# fpc.net
KiCad netlist of a schematic drawn in EAGLE
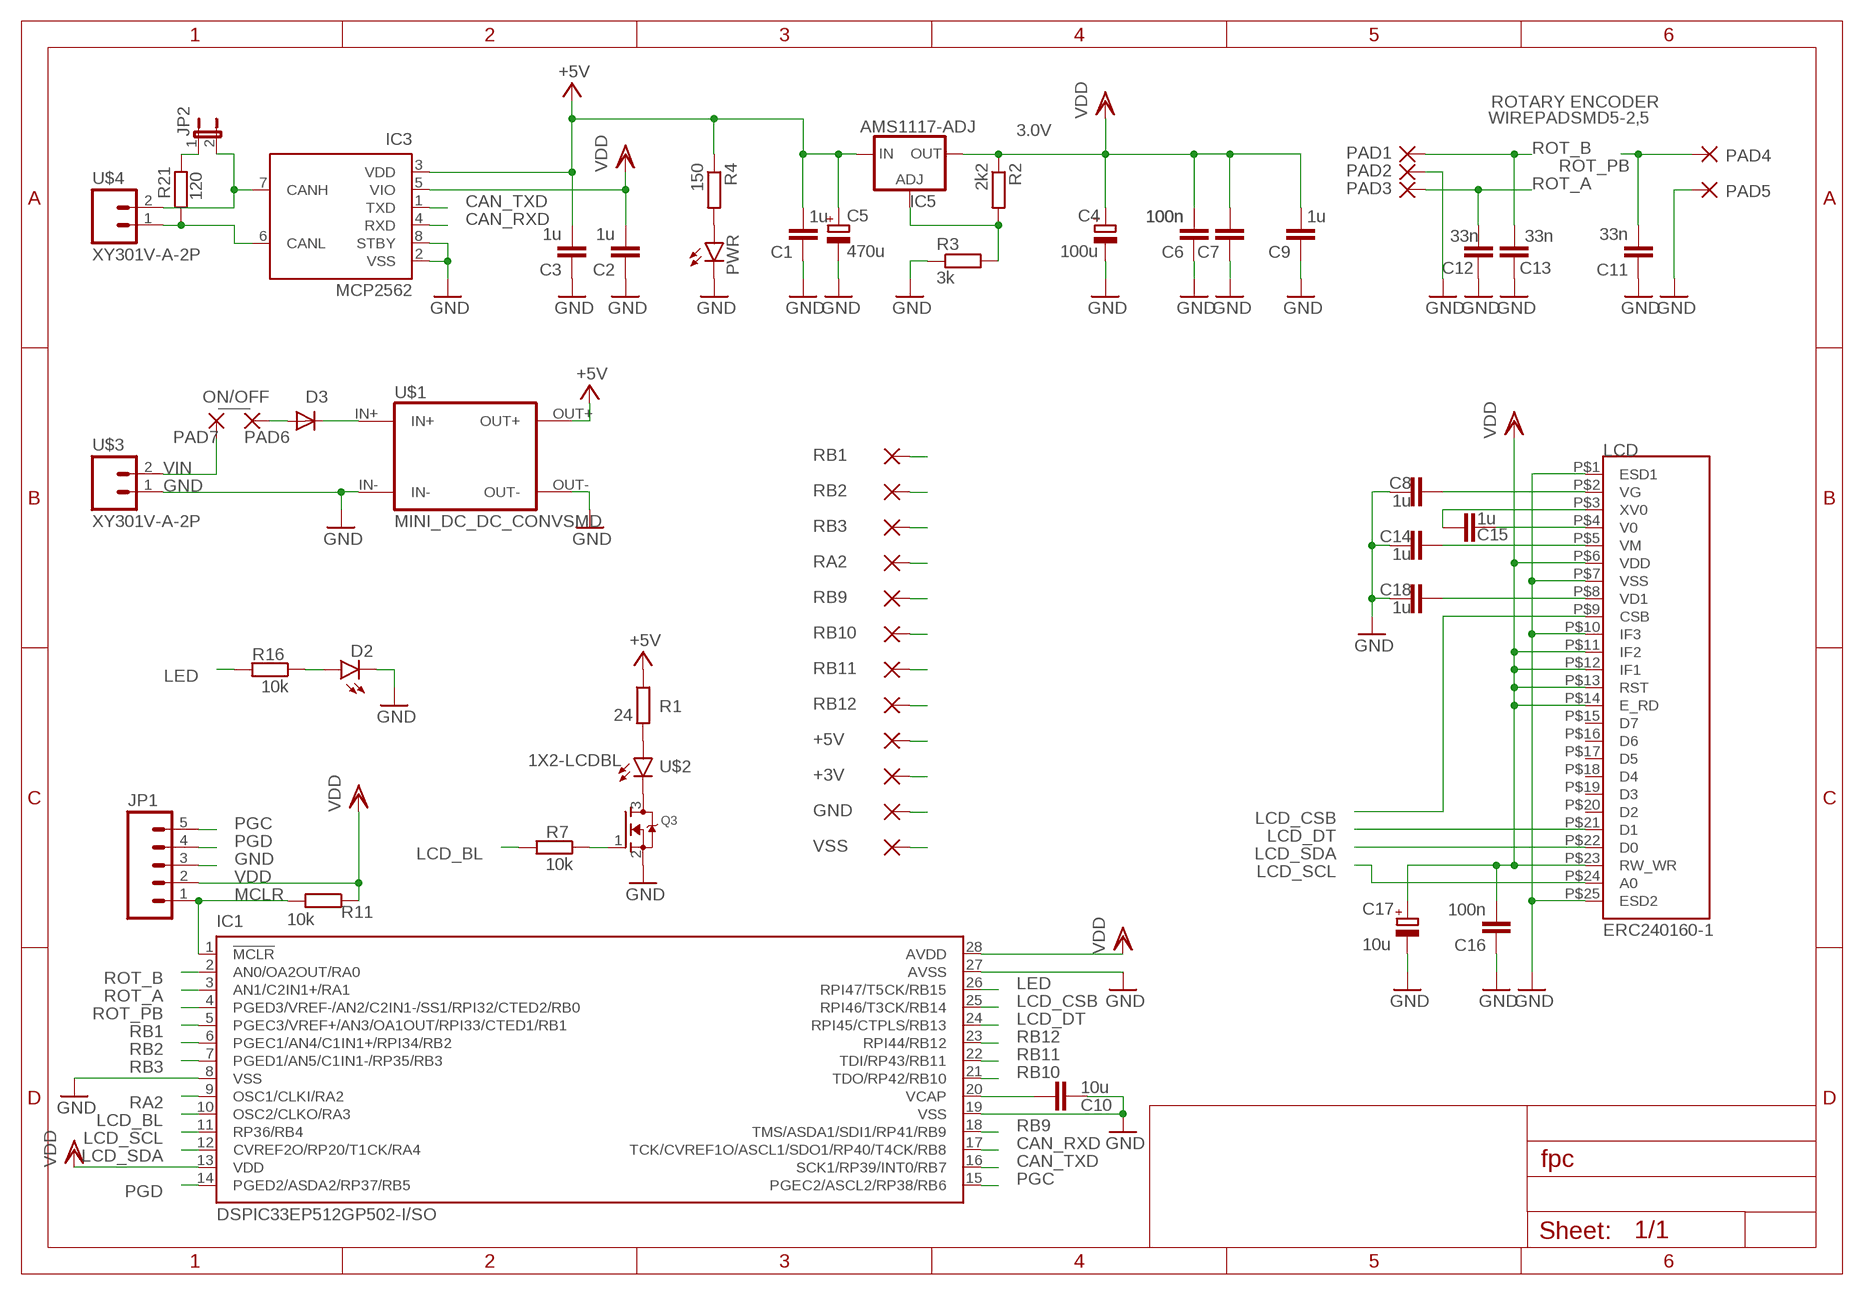
[diagram p0: schematic, sheet 1]

(export (version "E")
  (design (tool "Eeschema 10.0.6"))
  (components
    (comp (ref "+3V")
      (value "WIREPADSMD1,27-254")
      (footprint "eagle-import:SMD1,27-2,54")
      (libsource (lib "eagle-import") (part "WIREPADSMD1,27-254"))
    )
    (comp (ref "+5V")
      (value "WIREPADSMD1,27-254")
      (footprint "eagle-import:SMD1,27-2,54")
      (libsource (lib "eagle-import") (part "WIREPADSMD1,27-254"))
    )
    (comp (ref "C1")
      (value "1u")
      (footprint "eagle-import:C0603K")
      (libsource (lib "eagle-import") (part "C-EUC0603K"))
    )
    (comp (ref "C2")
      (value "1u")
      (footprint "eagle-import:C0603K")
      (libsource (lib "eagle-import") (part "C-EUC0603K"))
    )
    (comp (ref "C3")
      (value "1u")
      (footprint "eagle-import:C0603K")
      (libsource (lib "eagle-import") (part "C-EUC0603K"))
    )
    (comp (ref "C4")
      (value "100u")
      (footprint "eagle-import:SANYO-OSCON_SMD_B6")
      (libsource (lib "eagle-import") (part "CPOL-EUSANYO_SMD_B6"))
    )
    (comp (ref "C5")
      (value "470u")
      (footprint "eagle-import:SANYO-OSCON_SMD_B6")
      (libsource (lib "eagle-import") (part "CPOL-EUSANYO_SMD_B6"))
    )
    (comp (ref "C6")
      (value "100n")
      (footprint "eagle-import:C0603K")
      (libsource (lib "eagle-import") (part "C-EUC0603K"))
    )
    (comp (ref "C7")
      (value "100n")
      (footprint "eagle-import:C0603K")
      (libsource (lib "eagle-import") (part "C-EUC0603K"))
    )
    (comp (ref "C8")
      (value "1u")
      (footprint "eagle-import:C0603K")
      (libsource (lib "eagle-import") (part "C-EUC0603K"))
    )
    (comp (ref "C9")
      (value "1u")
      (footprint "eagle-import:C0603K")
      (libsource (lib "eagle-import") (part "C-EUC0603K"))
    )
    (comp (ref "C10")
      (value "10u")
      (footprint "eagle-import:C0805")
      (libsource (lib "eagle-import") (part "C-EUC0805"))
    )
    (comp (ref "C11")
      (value "33n")
      (footprint "eagle-import:C0603K")
      (libsource (lib "eagle-import") (part "C-EUC0603K"))
    )
    (comp (ref "C12")
      (value "33n")
      (footprint "eagle-import:C0603K")
      (libsource (lib "eagle-import") (part "C-EUC0603K"))
    )
    (comp (ref "C13")
      (value "33n")
      (footprint "eagle-import:C0603K")
      (libsource (lib "eagle-import") (part "C-EUC0603K"))
    )
    (comp (ref "C14")
      (value "1u")
      (footprint "eagle-import:C0603K")
      (libsource (lib "eagle-import") (part "C-EUC0603K"))
    )
    (comp (ref "C15")
      (value "1u")
      (footprint "eagle-import:C0603K")
      (libsource (lib "eagle-import") (part "C-EUC0603K"))
    )
    (comp (ref "C16")
      (value "100n")
      (footprint "eagle-import:C0603K")
      (libsource (lib "eagle-import") (part "C-EUC0603K"))
    )
    (comp (ref "C17")
      (value "10u")
      (footprint "eagle-import:SANYO-OSCON_SMD_E12")
      (libsource (lib "eagle-import") (part "CPOL-EUSANYO_SMD_E12"))
    )
    (comp (ref "C18")
      (value "1u")
      (footprint "eagle-import:C0603K")
      (libsource (lib "eagle-import") (part "C-EUC0603K"))
    )
    (comp (ref "D2")
      (value "LED-FKIT-1206")
      (footprint "eagle-import:FKIT-LED-1206")
      (libsource (lib "eagle-import") (part "LED-FKIT-1206"))
    )
    (comp (ref "D3")
      (value "DIODESMA")
      (footprint "eagle-import:SMADIODE")
      (libsource (lib "eagle-import") (part "DIODESMA"))
    )
    (comp (ref "GND")
      (value "WIREPADSMD1,27-254")
      (footprint "eagle-import:SMD1,27-2,54")
      (libsource (lib "eagle-import") (part "WIREPADSMD1,27-254"))
    )
    (comp (ref "IC1")
      (value "DSPIC33EP512GP502-I/SO")
      (footprint "eagle-import:SO28W")
      (libsource (lib "eagle-import") (part "DSPIC33EP502?-I/SO512GP"))
    )
    (comp (ref "IC3")
      (value "MCP2562")
      (footprint "eagle-import:SO-08")
      (libsource (lib "eagle-import") (part "MCP2562-E/SN"))
    )
    (comp (ref "IC5")
      (value "AMS1117-ADJ")
      (footprint "eagle-import:SOT223")
      (libsource (lib "eagle-import") (part "LD117A?S33TR"))
    )
    (comp (ref "JP1")
      (value "M05PTH")
      (footprint "eagle-import:1X05")
      (libsource (lib "eagle-import") (part "M05PTH"))
    )
    (comp (ref "JP2")
      (value "JP1E")
      (footprint "eagle-import:JP1")
      (libsource (lib "eagle-import") (part "JP1E"))
    )
    (comp (ref "LCD")
      (value "ERC240160-1")
      (footprint "eagle-import:1X25-LCDFPC-SMD")
      (libsource (lib "eagle-import") (part "ERC240160-1"))
    )
    (comp (ref "PAD1")
      (value "WIREPADSMD5-2,5")
      (footprint "eagle-import:5-2,5")
      (libsource (lib "eagle-import") (part "WIREPADSMD5-2,5"))
    )
    (comp (ref "PAD2")
      (value "WIREPADSMD5-2,5")
      (footprint "eagle-import:5-2,5")
      (libsource (lib "eagle-import") (part "WIREPADSMD5-2,5"))
    )
    (comp (ref "PAD3")
      (value "WIREPADSMD5-2,5")
      (footprint "eagle-import:5-2,5")
      (libsource (lib "eagle-import") (part "WIREPADSMD5-2,5"))
    )
    (comp (ref "PAD4")
      (value "WIREPADSMD5-2,5")
      (footprint "eagle-import:5-2,5")
      (libsource (lib "eagle-import") (part "WIREPADSMD5-2,5"))
    )
    (comp (ref "PAD5")
      (value "WIREPADSMD5-2,5")
      (footprint "eagle-import:5-2,5")
      (libsource (lib "eagle-import") (part "WIREPADSMD5-2,5"))
    )
    (comp (ref "PAD6")
      (value "WIREPADSMD5-2,5")
      (footprint "eagle-import:5-2,5")
      (libsource (lib "eagle-import") (part "WIREPADSMD5-2,5"))
    )
    (comp (ref "PAD7")
      (value "WIREPADSMD5-2,5")
      (footprint "eagle-import:5-2,5")
      (libsource (lib "eagle-import") (part "WIREPADSMD5-2,5"))
    )
    (comp (ref "PWR")
      (value "LED-FKIT-1206")
      (footprint "eagle-import:FKIT-LED-1206")
      (libsource (lib "eagle-import") (part "LED-FKIT-1206"))
    )
    (comp (ref "Q3")
      (value "MOSFET-NREFLOW")
      (footprint "eagle-import:SOT23")
      (libsource (lib "eagle-import") (part "MOSFET-NREFLOW"))
    )
    (comp (ref "R1")
      (value "24")
      (footprint "eagle-import:R0805")
      (libsource (lib "eagle-import") (part "R-EU_R0805"))
    )
    (comp (ref "R2")
      (value "2k2")
      (footprint "eagle-import:R0603")
      (libsource (lib "eagle-import") (part "R-EU_R0603"))
    )
    (comp (ref "R3")
      (value "3k")
      (footprint "eagle-import:R0603")
      (libsource (lib "eagle-import") (part "R-EU_R0603"))
    )
    (comp (ref "R4")
      (value "150")
      (footprint "eagle-import:R0603")
      (libsource (lib "eagle-import") (part "R-EU_R0603"))
    )
    (comp (ref "R7")
      (value "10k")
      (footprint "eagle-import:R0603")
      (libsource (lib "eagle-import") (part "R-EU_R0603"))
    )
    (comp (ref "R11")
      (value "10k")
      (footprint "eagle-import:R0603")
      (libsource (lib "eagle-import") (part "R-EU_R0603"))
    )
    (comp (ref "R16")
      (value "10k")
      (footprint "eagle-import:R0603")
      (libsource (lib "eagle-import") (part "R-EU_R0603"))
    )
    (comp (ref "R21")
      (value "120")
      (footprint "eagle-import:R0603")
      (libsource (lib "eagle-import") (part "R-EU_R0603"))
    )
    (comp (ref "RA2")
      (value "WIREPADSMD1,27-254")
      (footprint "eagle-import:SMD1,27-2,54")
      (libsource (lib "eagle-import") (part "WIREPADSMD1,27-254"))
    )
    (comp (ref "RB1")
      (value "WIREPADSMD1,27-254")
      (footprint "eagle-import:SMD1,27-2,54")
      (libsource (lib "eagle-import") (part "WIREPADSMD1,27-254"))
    )
    (comp (ref "RB2")
      (value "WIREPADSMD1,27-254")
      (footprint "eagle-import:SMD1,27-2,54")
      (libsource (lib "eagle-import") (part "WIREPADSMD1,27-254"))
    )
    (comp (ref "RB3")
      (value "WIREPADSMD1,27-254")
      (footprint "eagle-import:SMD1,27-2,54")
      (libsource (lib "eagle-import") (part "WIREPADSMD1,27-254"))
    )
    (comp (ref "RB9")
      (value "WIREPADSMD1,27-254")
      (footprint "eagle-import:SMD1,27-2,54")
      (libsource (lib "eagle-import") (part "WIREPADSMD1,27-254"))
    )
    (comp (ref "RB10")
      (value "WIREPADSMD1,27-254")
      (footprint "eagle-import:SMD1,27-2,54")
      (libsource (lib "eagle-import") (part "WIREPADSMD1,27-254"))
    )
    (comp (ref "RB11")
      (value "WIREPADSMD1,27-254")
      (footprint "eagle-import:SMD1,27-2,54")
      (libsource (lib "eagle-import") (part "WIREPADSMD1,27-254"))
    )
    (comp (ref "RB12")
      (value "WIREPADSMD1,27-254")
      (footprint "eagle-import:SMD1,27-2,54")
      (libsource (lib "eagle-import") (part "WIREPADSMD1,27-254"))
    )
    (comp (ref "U$1")
      (value "MINI_DC_DC_CONVSMD")
      (footprint "eagle-import:DSN-MINI-360-SMD")
      (libsource (lib "eagle-import") (part "MINI_DC_DC_CONVSMD"))
    )
    (comp (ref "U$2")
      (value "1X2-LCDBL")
      (footprint "eagle-import:1X2-LCDBL-SMD")
      (libsource (lib "eagle-import") (part "1X2-LCDBL"))
    )
    (comp (ref "U$3")
      (value "XY301V-A-2P")
      (footprint "eagle-import:XY301V-A-2P")
      (libsource (lib "eagle-import") (part "XY301V-A-2P"))
    )
    (comp (ref "U$4")
      (value "XY301V-A-2P")
      (footprint "eagle-import:XY301V-A-2P")
      (libsource (lib "eagle-import") (part "XY301V-A-2P"))
    )
    (comp (ref "VSS")
      (value "WIREPADSMD1,27-254")
      (footprint "eagle-import:SMD1,27-2,54")
      (libsource (lib "eagle-import") (part "WIREPADSMD1,27-254"))
    )
  )
  (nets
    (net (code "1") (name "+5V") (class "Default")
      (node (ref "+5V") (pin "1") (pinfunction "P_1") (pintype "passive"))
      (node (ref "C1") (pin "2") (pinfunction "2_2") (pintype "passive"))
      (node (ref "C3") (pin "2") (pinfunction "2_2") (pintype "passive"))
      (node (ref "C5") (pin "+") (pinfunction "+_+") (pintype "passive"))
      (node (ref "IC3") (pin "3") (pinfunction "VDD_3") (pintype "power_in"))
      (node (ref "IC5") (pin "3") (pinfunction "IN_3") (pintype "input"))
      (node (ref "R1") (pin "1") (pinfunction "1_1") (pintype "passive"))
      (node (ref "R4") (pin "1") (pinfunction "1_1") (pintype "passive"))
      (node (ref "U$1") (pin "OUT+") (pinfunction "OUT+_OUT+") (pintype "output"))
    )
    (net (code "2") (name "/CAN_RXD") (class "Default")
      (node (ref "IC1") (pin "17") (pinfunction "TCK/CVREF1O/ASCL1/SDO1/RP40/T4CK/RB8_17") (pintype "bidirectional"))
      (node (ref "IC3") (pin "4") (pinfunction "RXD_4") (pintype "output"))
    )
    (net (code "3") (name "/CAN_TXD") (class "Default")
      (node (ref "IC1") (pin "16") (pinfunction "SCK1/RP39/INT0/RB7_16") (pintype "bidirectional"))
      (node (ref "IC3") (pin "1") (pinfunction "TXD_1") (pintype "input"))
    )
    (net (code "4") (name "/LCD_BL") (class "Default")
      (node (ref "IC1") (pin "10") (pinfunction "OSC2/CLKO/RA3_10") (pintype "bidirectional"))
      (node (ref "R7") (pin "2") (pinfunction "2_2") (pintype "passive"))
    )
    (net (code "5") (name "/LCD_CSB") (class "Default")
      (node (ref "IC1") (pin "25") (pinfunction "RPI46/T3CK/RB14_25") (pintype "bidirectional"))
      (node (ref "LCD") (pin "P$9") (pinfunction "CSB_P$9") (pintype "bidirectional"))
    )
    (net (code "6") (name "/LCD_DT") (class "Default")
      (node (ref "IC1") (pin "24") (pinfunction "RPI45/CTPLS/RB13_24") (pintype "bidirectional"))
      (node (ref "LCD") (pin "P$21") (pinfunction "D1_P$21") (pintype "bidirectional"))
    )
    (net (code "7") (name "/LCD_SCL") (class "Default")
      (node (ref "IC1") (pin "11") (pinfunction "RP36/RB4_11") (pintype "bidirectional"))
      (node (ref "LCD") (pin "P$24") (pinfunction "A0_P$24") (pintype "bidirectional"))
    )
    (net (code "8") (name "/LCD_SDA") (class "Default")
      (node (ref "IC1") (pin "12") (pinfunction "CVREF2O/RP20/T1CK/RA4_12") (pintype "bidirectional"))
      (node (ref "LCD") (pin "P$22") (pinfunction "D0_P$22") (pintype "bidirectional"))
    )
    (net (code "9") (name "/LED") (class "Default")
      (node (ref "IC1") (pin "26") (pinfunction "RPI47/T5CK/RB15_26") (pintype "bidirectional"))
      (node (ref "R16") (pin "2") (pinfunction "2_2") (pintype "passive"))
    )
    (net (code "10") (name "/MCLR") (class "Default")
      (node (ref "IC1") (pin "1") (pinfunction "~{MCLR}_1") (pintype "input"))
      (node (ref "JP1") (pin "1") (pinfunction "1_1") (pintype "passive"))
      (node (ref "R11") (pin "2") (pinfunction "2_2") (pintype "passive"))
    )
    (net (code "11") (name "/PGC") (class "Default")
      (node (ref "IC1") (pin "15") (pinfunction "PGEC2/ASCL2/RP38/RB6_15") (pintype "bidirectional"))
      (node (ref "JP1") (pin "5") (pinfunction "5_5") (pintype "passive"))
    )
    (net (code "12") (name "/PGD") (class "Default")
      (node (ref "IC1") (pin "14") (pinfunction "PGED2/ASDA2/RP37/RB5_14") (pintype "bidirectional"))
      (node (ref "JP1") (pin "4") (pinfunction "4_4") (pintype "passive"))
    )
    (net (code "13") (name "/RA2") (class "Default")
      (node (ref "IC1") (pin "9") (pinfunction "OSC1/CLKI/RA2_9") (pintype "input"))
      (node (ref "RA2") (pin "1") (pinfunction "P_1") (pintype "passive"))
    )
    (net (code "14") (name "/RB1") (class "Default")
      (node (ref "IC1") (pin "5") (pinfunction "PGEC3/VREF+/AN3/OA1OUT/RPI33/CTED1/RB1_5") (pintype "bidirectional"))
      (node (ref "RB1") (pin "1") (pinfunction "P_1") (pintype "passive"))
    )
    (net (code "15") (name "/RB2") (class "Default")
      (node (ref "IC1") (pin "6") (pinfunction "PGEC1/AN4/C1IN1+/RPI34/RB2_6") (pintype "bidirectional"))
      (node (ref "RB2") (pin "1") (pinfunction "P_1") (pintype "passive"))
    )
    (net (code "16") (name "/RB3") (class "Default")
      (node (ref "IC1") (pin "7") (pinfunction "PGED1/AN5/C1IN1-/RP35/RB3_7") (pintype "bidirectional"))
      (node (ref "RB3") (pin "1") (pinfunction "P_1") (pintype "passive"))
    )
    (net (code "17") (name "/RB9") (class "Default")
      (node (ref "IC1") (pin "18") (pinfunction "TMS/ASDA1/SDI1/RP41/RB9_18") (pintype "bidirectional"))
      (node (ref "RB9") (pin "1") (pinfunction "P_1") (pintype "passive"))
    )
    (net (code "18") (name "/RB10") (class "Default")
      (node (ref "IC1") (pin "21") (pinfunction "TDO/RP42/RB10_21") (pintype "bidirectional"))
      (node (ref "RB10") (pin "1") (pinfunction "P_1") (pintype "passive"))
    )
    (net (code "19") (name "/RB11") (class "Default")
      (node (ref "IC1") (pin "22") (pinfunction "TDI/RP43/RB11_22") (pintype "bidirectional"))
      (node (ref "RB11") (pin "1") (pinfunction "P_1") (pintype "passive"))
    )
    (net (code "20") (name "/RB12") (class "Default")
      (node (ref "IC1") (pin "23") (pinfunction "RPI44/RB12_23") (pintype "bidirectional"))
      (node (ref "RB12") (pin "1") (pinfunction "P_1") (pintype "passive"))
    )
    (net (code "21") (name "/ROT_A") (class "Default")
      (node (ref "C12") (pin "2") (pinfunction "2_2") (pintype "passive"))
      (node (ref "IC1") (pin "3") (pinfunction "AN1/C2IN1+/RA1_3") (pintype "bidirectional"))
      (node (ref "PAD3") (pin "1") (pinfunction "P_1") (pintype "passive"))
    )
    (net (code "22") (name "/ROT_B") (class "Default")
      (node (ref "C13") (pin "2") (pinfunction "2_2") (pintype "passive"))
      (node (ref "IC1") (pin "2") (pinfunction "AN0/OA2OUT/RA0_2") (pintype "bidirectional"))
      (node (ref "PAD1") (pin "1") (pinfunction "P_1") (pintype "passive"))
    )
    (net (code "23") (name "/ROT_PB") (class "Default")
      (node (ref "C11") (pin "2") (pinfunction "2_2") (pintype "passive"))
      (node (ref "IC1") (pin "4") (pinfunction "PGED3/VREF-/AN2/C2IN1-/SS1/RPI32/CTED2/RB0_4") (pintype "bidirectional"))
      (node (ref "PAD4") (pin "1") (pinfunction "P_1") (pintype "passive"))
    )
    (net (code "24") (name "/VIN") (class "Default")
      (node (ref "PAD7") (pin "1") (pinfunction "P_1") (pintype "passive"))
      (node (ref "U$3") (pin "2") (pinfunction "2_2") (pintype "passive"))
    )
    (net (code "25") (name "GND") (class "Default")
      (node (ref "C1") (pin "1") (pinfunction "1_1") (pintype "passive"))
      (node (ref "C10") (pin "1") (pinfunction "1_1") (pintype "passive"))
      (node (ref "C11") (pin "1") (pinfunction "1_1") (pintype "passive"))
      (node (ref "C12") (pin "1") (pinfunction "1_1") (pintype "passive"))
      (node (ref "C13") (pin "1") (pinfunction "1_1") (pintype "passive"))
      (node (ref "C14") (pin "1") (pinfunction "1_1") (pintype "passive"))
      (node (ref "C16") (pin "1") (pinfunction "1_1") (pintype "passive"))
      (node (ref "C17") (pin "-") (pinfunction "-_-") (pintype "passive"))
      (node (ref "C18") (pin "1") (pinfunction "1_1") (pintype "passive"))
      (node (ref "C2") (pin "1") (pinfunction "1_1") (pintype "passive"))
      (node (ref "C3") (pin "1") (pinfunction "1_1") (pintype "passive"))
      (node (ref "C4") (pin "-") (pinfunction "-_-") (pintype "passive"))
      (node (ref "C5") (pin "-") (pinfunction "-_-") (pintype "passive"))
      (node (ref "C6") (pin "1") (pinfunction "1_1") (pintype "passive"))
      (node (ref "C7") (pin "1") (pinfunction "1_1") (pintype "passive"))
      (node (ref "C8") (pin "1") (pinfunction "1_1") (pintype "passive"))
      (node (ref "C9") (pin "1") (pinfunction "1_1") (pintype "passive"))
      (node (ref "D2") (pin "C") (pinfunction "C_C") (pintype "passive"))
      (node (ref "GND") (pin "1") (pinfunction "P_1") (pintype "passive"))
      (node (ref "IC1") (pin "19") (pinfunction "VSS_19") (pintype "power_in"))
      (node (ref "IC1") (pin "27") (pinfunction "AVSS_27") (pintype "power_in"))
      (node (ref "IC1") (pin "8") (pinfunction "VSS_8") (pintype "power_in"))
      (node (ref "IC3") (pin "2") (pinfunction "VSS_2") (pintype "power_in"))
      (node (ref "IC3") (pin "8") (pinfunction "STBY_8") (pintype "input"))
      (node (ref "JP1") (pin "3") (pinfunction "3_3") (pintype "passive"))
      (node (ref "LCD") (pin "P$1") (pinfunction "ESD1_P$1") (pintype "bidirectional"))
      (node (ref "LCD") (pin "P$10") (pinfunction "IF3_P$10") (pintype "bidirectional"))
      (node (ref "LCD") (pin "P$25") (pinfunction "ESD2_P$25") (pintype "bidirectional"))
      (node (ref "LCD") (pin "P$7") (pinfunction "VSS_P$7") (pintype "bidirectional"))
      (node (ref "PAD2") (pin "1") (pinfunction "P_1") (pintype "passive"))
      (node (ref "PAD5") (pin "1") (pinfunction "P_1") (pintype "passive"))
      (node (ref "PWR") (pin "C") (pinfunction "C_C") (pintype "passive"))
      (node (ref "Q3") (pin "2") (pinfunction "S_2") (pintype "bidirectional"))
      (node (ref "R3") (pin "1") (pinfunction "1_1") (pintype "passive"))
      (node (ref "U$1") (pin "IN-") (pinfunction "IN-_IN-") (pintype "power_in"))
      (node (ref "U$1") (pin "OUT-") (pinfunction "OUT-_OUT-") (pintype "power_in"))
      (node (ref "U$3") (pin "1") (pinfunction "1_1") (pintype "passive"))
      (node (ref "VSS") (pin "1") (pinfunction "P_1") (pintype "passive"))
    )
    (net (code "26") (name "Net-(D2-PadA)") (class "Default")
      (node (ref "D2") (pin "A") (pinfunction "A_A") (pintype "passive"))
      (node (ref "R16") (pin "1") (pinfunction "1_1") (pintype "passive"))
    )
    (net (code "27") (name "Net-(D3-PadC)") (class "Default")
      (node (ref "D3") (pin "C") (pinfunction "C_C") (pintype "passive"))
      (node (ref "U$1") (pin "IN+") (pinfunction "IN+_IN+") (pintype "input"))
    )
    (net (code "28") (name "Net-(IC1-VCAP)") (class "Default")
      (node (ref "C10") (pin "2") (pinfunction "2_2") (pintype "passive"))
      (node (ref "IC1") (pin "20") (pinfunction "VCAP_20") (pintype "power_in"))
    )
    (net (code "29") (name "Net-(IC3-CANH)") (class "Default")
      (node (ref "IC3") (pin "7") (pinfunction "CANH_7") (pintype "bidirectional"))
      (node (ref "JP2") (pin "2") (pinfunction "2_2") (pintype "passive"))
      (node (ref "U$4") (pin "2") (pinfunction "2_2") (pintype "passive"))
    )
    (net (code "30") (name "Net-(IC3-CANL)") (class "Default")
      (node (ref "IC3") (pin "6") (pinfunction "CANL_6") (pintype "bidirectional"))
      (node (ref "R21") (pin "1") (pinfunction "1_1") (pintype "passive"))
      (node (ref "U$4") (pin "1") (pinfunction "1_1") (pintype "passive"))
    )
    (net (code "31") (name "Net-(IC5-ADJ)") (class "Default")
      (node (ref "IC5") (pin "1") (pinfunction "ADJ_1") (pintype "input"))
      (node (ref "R2") (pin "2") (pinfunction "2_2") (pintype "passive"))
      (node (ref "R3") (pin "2") (pinfunction "2_2") (pintype "passive"))
    )
    (net (code "32") (name "Net-(JP2-Pad1)") (class "Default")
      (node (ref "JP2") (pin "1") (pinfunction "1_1") (pintype "passive"))
      (node (ref "R21") (pin "2") (pinfunction "2_2") (pintype "passive"))
    )
    (net (code "33") (name "Net-(LCD-V0)") (class "Default")
      (node (ref "C15") (pin "2") (pinfunction "2_2") (pintype "passive"))
      (node (ref "LCD") (pin "P$4") (pinfunction "V0_P$4") (pintype "bidirectional"))
    )
    (net (code "34") (name "Net-(LCD-VD1)") (class "Default")
      (node (ref "C18") (pin "2") (pinfunction "2_2") (pintype "passive"))
      (node (ref "LCD") (pin "P$8") (pinfunction "VD1_P$8") (pintype "bidirectional"))
    )
    (net (code "35") (name "Net-(LCD-VG)") (class "Default")
      (node (ref "C8") (pin "2") (pinfunction "2_2") (pintype "passive"))
      (node (ref "LCD") (pin "P$2") (pinfunction "VG_P$2") (pintype "bidirectional"))
    )
    (net (code "36") (name "Net-(LCD-VM)") (class "Default")
      (node (ref "C14") (pin "2") (pinfunction "2_2") (pintype "passive"))
      (node (ref "LCD") (pin "P$5") (pinfunction "VM_P$5") (pintype "bidirectional"))
    )
    (net (code "37") (name "Net-(LCD-XV0)") (class "Default")
      (node (ref "C15") (pin "1") (pinfunction "1_1") (pintype "passive"))
      (node (ref "LCD") (pin "P$3") (pinfunction "XV0_P$3") (pintype "bidirectional"))
    )
    (net (code "38") (name "Net-(PAD6-P)") (class "Default")
      (node (ref "D3") (pin "A") (pinfunction "A_A") (pintype "passive"))
      (node (ref "PAD6") (pin "1") (pinfunction "P_1") (pintype "passive"))
    )
    (net (code "39") (name "Net-(PWR-PadA)") (class "Default")
      (node (ref "PWR") (pin "A") (pinfunction "A_A") (pintype "passive"))
      (node (ref "R4") (pin "2") (pinfunction "2_2") (pintype "passive"))
    )
    (net (code "40") (name "Net-(Q3-D)") (class "Default")
      (node (ref "Q3") (pin "3") (pinfunction "D_3") (pintype "bidirectional"))
      (node (ref "U$2") (pin "K") (pinfunction "C_K") (pintype "passive"))
    )
    (net (code "41") (name "Net-(Q3-G)") (class "Default")
      (node (ref "Q3") (pin "1") (pinfunction "G_1") (pintype "bidirectional"))
      (node (ref "R7") (pin "1") (pinfunction "1_1") (pintype "passive"))
    )
    (net (code "42") (name "Net-(R1-Pad2)") (class "Default")
      (node (ref "R1") (pin "2") (pinfunction "2_2") (pintype "passive"))
      (node (ref "U$2") (pin "A") (pinfunction "A_A") (pintype "passive"))
    )
    (net (code "43") (name "VDD") (class "Default")
      (node (ref "+3V") (pin "1") (pinfunction "P_1") (pintype "passive"))
      (node (ref "C16") (pin "2") (pinfunction "2_2") (pintype "passive"))
      (node (ref "C17") (pin "+") (pinfunction "+_+") (pintype "passive"))
      (node (ref "C2") (pin "2") (pinfunction "2_2") (pintype "passive"))
      (node (ref "C4") (pin "+") (pinfunction "+_+") (pintype "passive"))
      (node (ref "C6") (pin "2") (pinfunction "2_2") (pintype "passive"))
      (node (ref "C7") (pin "2") (pinfunction "2_2") (pintype "passive"))
      (node (ref "C9") (pin "2") (pinfunction "2_2") (pintype "passive"))
      (node (ref "IC1") (pin "13") (pinfunction "VDD_13") (pintype "power_in"))
      (node (ref "IC1") (pin "28") (pinfunction "AVDD_28") (pintype "power_in"))
      (node (ref "IC3") (pin "5") (pinfunction "VIO_5") (pintype "power_in"))
      (node (ref "IC5") (pin "2") (pinfunction "OUT_2") (pintype "passive"))
      (node (ref "IC5") (pin "@2") (pinfunction "OUT_@2") (pintype "passive"))
      (node (ref "JP1") (pin "2") (pinfunction "2_2") (pintype "passive"))
      (node (ref "LCD") (pin "P$11") (pinfunction "IF2_P$11") (pintype "bidirectional"))
      (node (ref "LCD") (pin "P$12") (pinfunction "IF1_P$12") (pintype "bidirectional"))
      (node (ref "LCD") (pin "P$13") (pinfunction "RST_P$13") (pintype "bidirectional"))
      (node (ref "LCD") (pin "P$14") (pinfunction "E_RD_P$14") (pintype "bidirectional"))
      (node (ref "LCD") (pin "P$23") (pinfunction "RW_WR_P$23") (pintype "bidirectional"))
      (node (ref "LCD") (pin "P$6") (pinfunction "VDD_P$6") (pintype "bidirectional"))
      (node (ref "R11") (pin "1") (pinfunction "1_1") (pintype "passive"))
      (node (ref "R2") (pin "1") (pinfunction "1_1") (pintype "passive"))
    )
    (net (code "44") (name "unconnected-(LCD-D2-PadP$20)") (class "Default")
      (node (ref "LCD") (pin "P$20") (pinfunction "D2_P$20") (pintype "bidirectional"))
    )
    (net (code "45") (name "unconnected-(LCD-D3-PadP$19)") (class "Default")
      (node (ref "LCD") (pin "P$19") (pinfunction "D3_P$19") (pintype "bidirectional"))
    )
    (net (code "46") (name "unconnected-(LCD-D4-PadP$18)") (class "Default")
      (node (ref "LCD") (pin "P$18") (pinfunction "D4_P$18") (pintype "bidirectional"))
    )
    (net (code "47") (name "unconnected-(LCD-D5-PadP$17)") (class "Default")
      (node (ref "LCD") (pin "P$17") (pinfunction "D5_P$17") (pintype "bidirectional"))
    )
    (net (code "48") (name "unconnected-(LCD-D6-PadP$16)") (class "Default")
      (node (ref "LCD") (pin "P$16") (pinfunction "D6_P$16") (pintype "bidirectional"))
    )
    (net (code "49") (name "unconnected-(LCD-D7-PadP$15)") (class "Default")
      (node (ref "LCD") (pin "P$15") (pinfunction "D7_P$15") (pintype "bidirectional"))
    )
  )
)
